# PDOC.net
KiCad netlist of a schematic drawn in Altium Designer
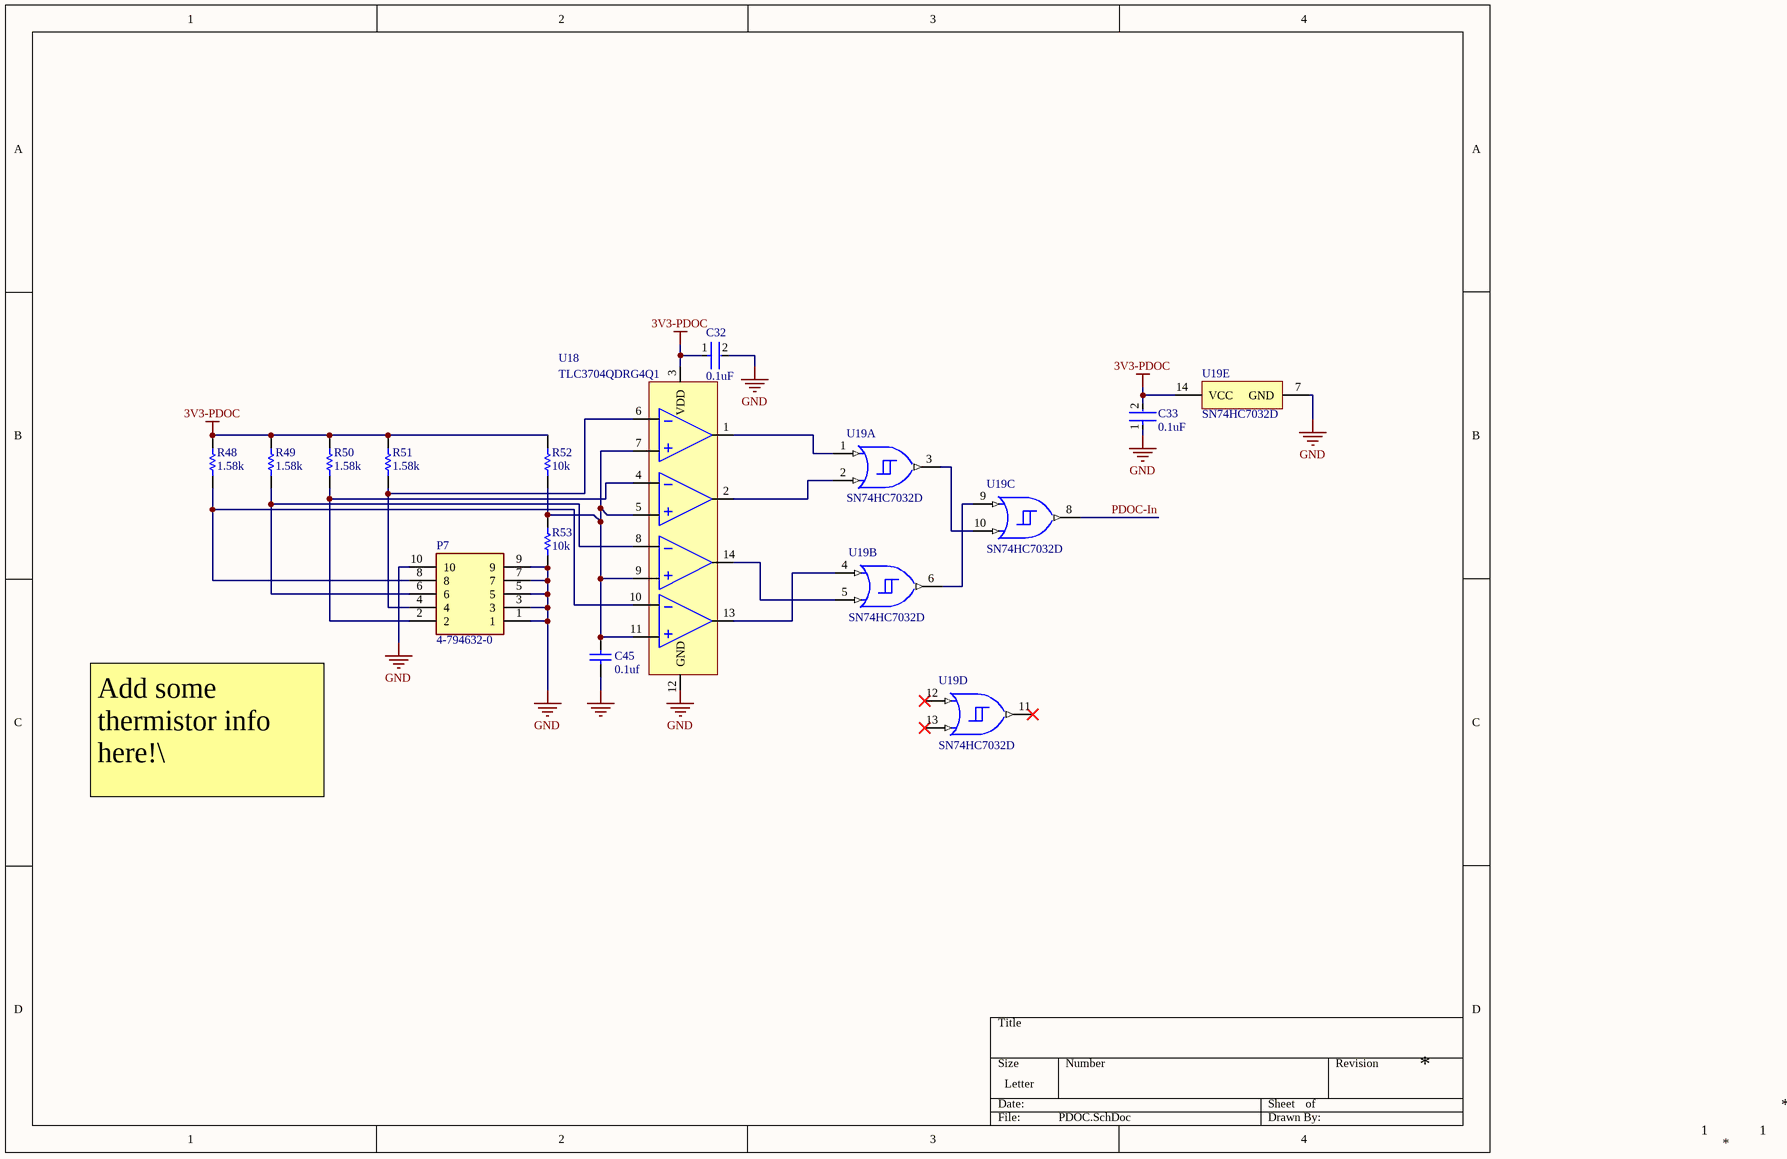
[diagram p0: PDOC.SchDoc]

(export (version "E")
  (design (tool "Eeschema 10.0.6"))
  (components
    (comp (ref "C32")
      (value "0.1uF")
      (footprint "FP-C0603-CJ-MFG")
      (description "CAP CER 0.1UF 50V X7R 0603")
      (fields (field (name "MANUFACTURER PART NUMBER") "C0603X104K5RACTU") (field (name "VOLTAGE") "50V"))
      (libsource (lib "Altium Content Vault") (part "11868f565c42a9108669ba33697ecf6"))
    )
    (comp (ref "C33")
      (value "0.1uF")
      (footprint "FP-C0603-CJ-MFG")
      (description "CAP CER 0.1UF 50V X7R 0603")
      (fields (field (name "MANUFACTURER PART NUMBER") "C0603X104K5RACTU") (field (name "VOLTAGE") "50V"))
      (libsource (lib "Altium Content Vault") (part "11868f565c42a9108669ba33697ecf6"))
    )
    (comp (ref "C45")
      (value "0.1uf")
      (footprint "CAPC1608X95N")
      (description "264-4630")
      (fields (field (name "Comment") "Cap") (field (name "PUBLISHER") "Altium Limited"))
      (libsource (lib "Miscellaneous Devices") (part "Cap"))
    )
    (comp (ref "P7")
      (value "4-794632-0")
      (footprint "SamacSys:SHDR10W82P300_2X5_1586X686X944P")
      (description "Connector")
      (fields (field (name "MOUSER PART NUMBER") "571-4-794632-0"))
      (libsource (lib "SamacSys") (part "4-794632-0"))
    )
    (comp (ref "R48")
      (value "1.58k")
      (footprint "RESC1608X55N")
      (description "1.58k 0805 1% 1/8W")
      (fields (field (name "TOLERANCE") "1%"))
      (libsource (lib "Resistors") (part "RC0805FR-071K58L"))
    )
    (comp (ref "R49")
      (value "1.58k")
      (footprint "RESC1608X55N")
      (description "1.58k 0805 1% 1/8W")
      (fields (field (name "TOLERANCE") "1%"))
      (libsource (lib "Resistors") (part "RC0805FR-071K58L"))
    )
    (comp (ref "R50")
      (value "1.58k")
      (footprint "RESC1608X55N")
      (description "1.58k 0805 1% 1/8W")
      (fields (field (name "TOLERANCE") "1%"))
      (libsource (lib "Resistors") (part "RC0805FR-071K58L"))
    )
    (comp (ref "R51")
      (value "1.58k")
      (footprint "RESC1608X55N")
      (description "1.58k 0805 1% 1/8W")
      (fields (field (name "TOLERANCE") "1%"))
      (libsource (lib "Resistors") (part "RC0805FR-071K58L"))
    )
    (comp (ref "R52")
      (value "10k")
      (footprint "RESC1608X55N")
      (description "10k E0805 1% 1/8W")
      (fields (field (name "TOLERANCE") "5%"))
      (libsource (lib "Resistors") (part "RC0805JR-0710KL"))
    )
    (comp (ref "R53")
      (value "10k")
      (footprint "RESC1608X55N")
      (description "10k E0805 1% 1/8W")
      (fields (field (name "TOLERANCE") "5%"))
      (libsource (lib "Resistors") (part "RC0805JR-0710KL"))
    )
    (comp (ref "U18")
      (value "TLC3704QDRG4Q1")
      (footprint "SOIC14")
      (description "IC VOLT COMPARATOR QUAD 14-SOIC")
      (libsource (lib "Logic") (part "TLC3704QDRG4Q1"))
    )
    (comp (ref "U19")
      (value "SN74HC7032D")
      (footprint "D0014A_L")
      (description "Quadruple Positive-OR Gates With Schmitt-Trigger Inputs, D0014A, TUBE")
      (fields
        (field (name "GENERIC PART NUMBER") "SN74HC7032")
        (field (name "MANUFACTURER") "Texas Instruments")
      )
      (libsource (lib "Altium Content Vault") (part "TI-SN74HC7032-D0014A-14"))
    )
  )
  (nets
    (net (code "1") (name "/PDOC-In") (class "Default")
      (node (ref "U19") (pin "8") (pinfunction "3Y_8") (pintype "output"))
    )
    (net (code "2") (name "3V3-PDOC") (class "Default")
      (node (ref "C32") (pin "1") (pinfunction "1_1") (pintype "passive"))
      (node (ref "C33") (pin "2") (pinfunction "2_2") (pintype "passive"))
      (node (ref "R48") (pin "2") (pinfunction "2_2") (pintype "passive"))
      (node (ref "R49") (pin "2") (pinfunction "2_2") (pintype "passive"))
      (node (ref "R50") (pin "2") (pinfunction "2_2") (pintype "passive"))
      (node (ref "R51") (pin "2") (pinfunction "2_2") (pintype "passive"))
      (node (ref "R52") (pin "2") (pinfunction "2_2") (pintype "passive"))
      (node (ref "U18") (pin "3") (pinfunction "VDD_3") (pintype "passive"))
      (node (ref "U19") (pin "14") (pinfunction "VCC_14") (pintype "power_in"))
    )
    (net (code "3") (name "GND") (class "Default")
      (node (ref "C32") (pin "2") (pinfunction "2_2") (pintype "passive"))
      (node (ref "C33") (pin "1") (pinfunction "1_1") (pintype "passive"))
      (node (ref "C45") (pin "1") (pinfunction "1_1") (pintype "passive"))
      (node (ref "P7") (pin "1") (pinfunction "1_1") (pintype "passive"))
      (node (ref "P7") (pin "10") (pinfunction "10_10") (pintype "passive"))
      (node (ref "P7") (pin "3") (pinfunction "3_3") (pintype "passive"))
      (node (ref "P7") (pin "5") (pinfunction "5_5") (pintype "passive"))
      (node (ref "P7") (pin "7") (pinfunction "7_7") (pintype "passive"))
      (node (ref "P7") (pin "9") (pinfunction "9_9") (pintype "passive"))
      (node (ref "R53") (pin "1") (pinfunction "1_1") (pintype "passive"))
      (node (ref "U18") (pin "12") (pinfunction "GND_12") (pintype "passive"))
      (node (ref "U19") (pin "7") (pinfunction "GND_7") (pintype "power_in"))
    )
    (net (code "4") (name "Net-(U18-In1+)") (class "Default")
      (node (ref "C45") (pin "2") (pinfunction "2_2") (pintype "passive"))
      (node (ref "R52") (pin "1") (pinfunction "1_1") (pintype "passive"))
      (node (ref "R53") (pin "2") (pinfunction "2_2") (pintype "passive"))
      (node (ref "U18") (pin "11") (pinfunction "In4+_11") (pintype "passive"))
      (node (ref "U18") (pin "5") (pinfunction "In2+_5") (pintype "passive"))
      (node (ref "U18") (pin "7") (pinfunction "In1+_7") (pintype "passive"))
      (node (ref "U18") (pin "9") (pinfunction "In3+_9") (pintype "passive"))
    )
    (net (code "5") (name "Net-(U18-In1-)") (class "Default")
      (node (ref "P7") (pin "4") (pinfunction "4_4") (pintype "passive"))
      (node (ref "R51") (pin "1") (pinfunction "1_1") (pintype "passive"))
      (node (ref "U18") (pin "6") (pinfunction "In1-_6") (pintype "passive"))
    )
    (net (code "6") (name "Net-(U18-In2-)") (class "Default")
      (node (ref "P7") (pin "2") (pinfunction "2_2") (pintype "passive"))
      (node (ref "R50") (pin "1") (pinfunction "1_1") (pintype "passive"))
      (node (ref "U18") (pin "4") (pinfunction "In2-_4") (pintype "passive"))
    )
    (net (code "7") (name "Net-(U18-In3-)") (class "Default")
      (node (ref "P7") (pin "6") (pinfunction "6_6") (pintype "passive"))
      (node (ref "R49") (pin "1") (pinfunction "1_1") (pintype "passive"))
      (node (ref "U18") (pin "8") (pinfunction "In3-_8") (pintype "passive"))
    )
    (net (code "8") (name "Net-(U18-In4-)") (class "Default")
      (node (ref "P7") (pin "8") (pinfunction "8_8") (pintype "passive"))
      (node (ref "R48") (pin "1") (pinfunction "1_1") (pintype "passive"))
      (node (ref "U18") (pin "10") (pinfunction "In4-_10") (pintype "passive"))
    )
    (net (code "9") (name "Net-(U18-Out1)") (class "Default")
      (node (ref "U18") (pin "1") (pinfunction "Out1_1") (pintype "passive"))
      (node (ref "U19") (pin "1") (pinfunction "1A_1") (pintype "input"))
    )
    (net (code "10") (name "Net-(U18-Out2)") (class "Default")
      (node (ref "U18") (pin "2") (pinfunction "Out2_2") (pintype "passive"))
      (node (ref "U19") (pin "2") (pinfunction "1B_2") (pintype "input"))
    )
    (net (code "11") (name "Net-(U18-Out3)") (class "Default")
      (node (ref "U18") (pin "14") (pinfunction "Out3_14") (pintype "passive"))
      (node (ref "U19") (pin "5") (pinfunction "2B_5") (pintype "input"))
    )
    (net (code "12") (name "Net-(U18-Out4)") (class "Default")
      (node (ref "U18") (pin "13") (pinfunction "Out4_13") (pintype "passive"))
      (node (ref "U19") (pin "4") (pinfunction "2A_4") (pintype "input"))
    )
    (net (code "13") (name "Net-(U19A-1Y)") (class "Default")
      (node (ref "U19") (pin "10") (pinfunction "3B_10") (pintype "input"))
      (node (ref "U19") (pin "3") (pinfunction "1Y_3") (pintype "output"))
    )
    (net (code "14") (name "Net-(U19B-2Y)") (class "Default")
      (node (ref "U19") (pin "6") (pinfunction "2Y_6") (pintype "output"))
      (node (ref "U19") (pin "9") (pinfunction "3A_9") (pintype "input"))
    )
    (net (code "15") (name "unconnected-(U19D-4A-Pad12)") (class "Default")
      (node (ref "U19") (pin "12") (pinfunction "4A_12") (pintype "input+no_connect"))
    )
    (net (code "16") (name "unconnected-(U19D-4B-Pad13)") (class "Default")
      (node (ref "U19") (pin "13") (pinfunction "4B_13") (pintype "input+no_connect"))
    )
    (net (code "17") (name "unconnected-(U19D-4Y-Pad11)") (class "Default")
      (node (ref "U19") (pin "11") (pinfunction "4Y_11") (pintype "output+no_connect"))
    )
  )
)
